# LEDs.net
KiCad netlist of a schematic drawn in Altium Designer
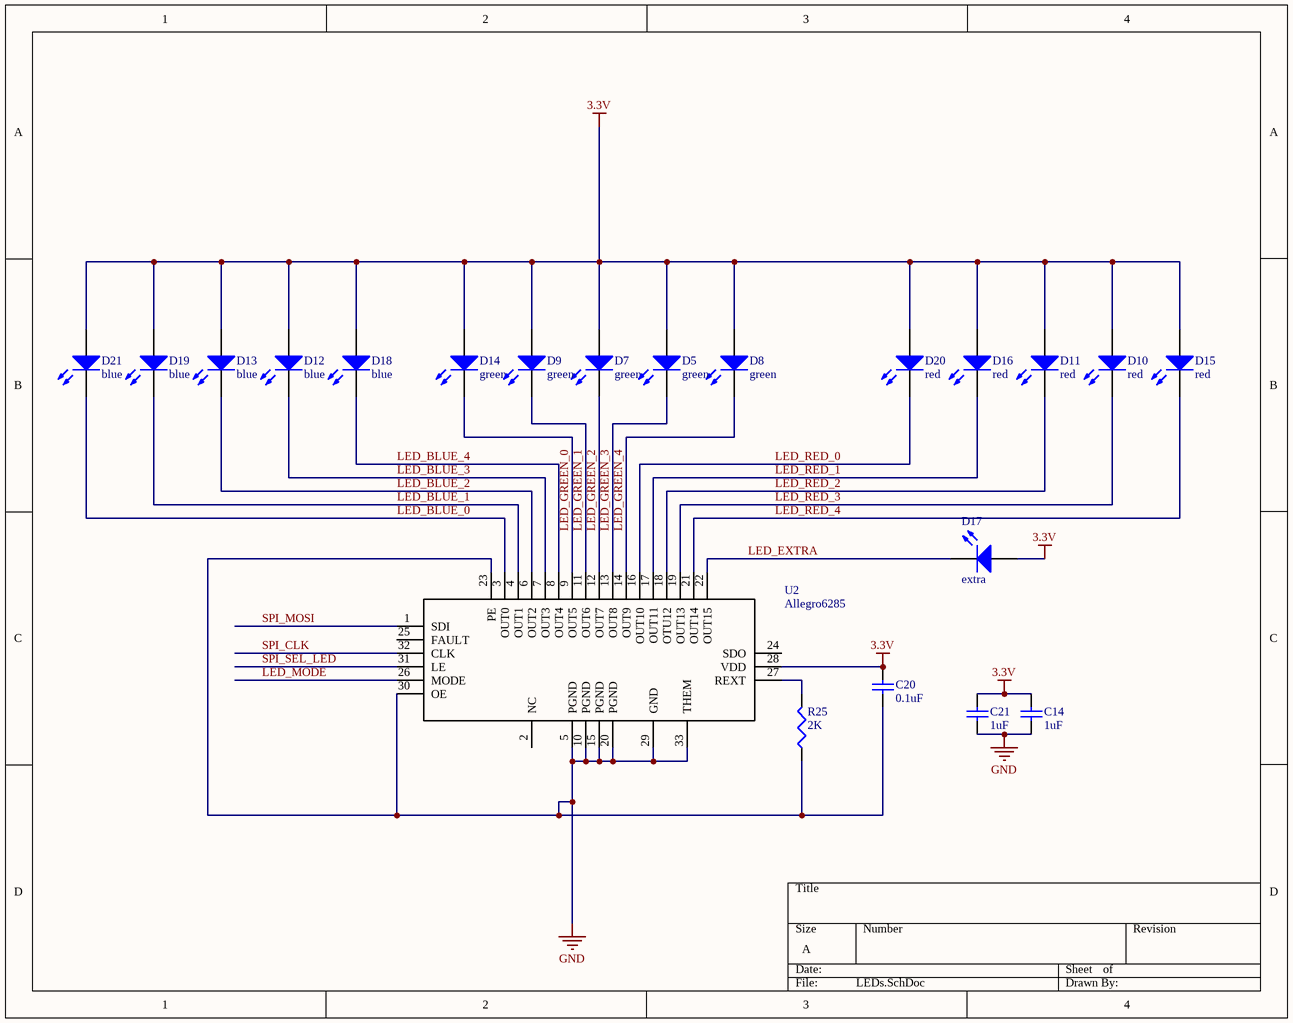
[diagram p0: LEDs.SchDoc]

(export (version "E")
  (design (tool "Eeschema 10.0.6"))
  (components
    (comp (ref "C14")
      (value "1uF")
      (footprint "CAPC1608L")
      (description "Capacitor (Semiconductor SIM Model)")
      (fields (field (name "Comment") "Cap Semi") (field (name "PUBLISHER") "Altium Limited"))
      (libsource (lib "Miscellaneous Devices") (part "Cap Semi"))
    )
    (comp (ref "C20")
      (value "0.1uF")
      (footprint "CAPC1005L")
      (description "Capacitor (Semiconductor SIM Model)")
      (fields (field (name "Comment") "Cap Semi") (field (name "PUBLISHER") "Altium Limited"))
      (libsource (lib "Miscellaneous Devices") (part "Cap Semi"))
    )
    (comp (ref "C21")
      (value "1uF")
      (footprint "CAPC1608L")
      (description "Capacitor (Semiconductor SIM Model)")
      (fields (field (name "Comment") "Cap Semi") (field (name "PUBLISHER") "Altium Limited"))
      (libsource (lib "Miscellaneous Devices") (part "Cap Semi"))
    )
    (comp (ref "D5") (value "green") (footprint "SurfaceMount(603)") (libsource (lib "mrone") (part "LED")))
    (comp (ref "D7") (value "green") (footprint "SurfaceMount(603)") (libsource (lib "mrone") (part "LED")))
    (comp (ref "D8") (value "green") (footprint "SurfaceMount(603)") (libsource (lib "mrone") (part "LED")))
    (comp (ref "D9") (value "green") (footprint "SurfaceMount(603)") (libsource (lib "mrone") (part "LED")))
    (comp (ref "D10") (value "red") (footprint "SurfaceMount(603)") (libsource (lib "mrone") (part "LED")))
    (comp (ref "D11") (value "red") (footprint "SurfaceMount(603)") (libsource (lib "mrone") (part "LED")))
    (comp (ref "D12") (value "blue") (footprint "SurfaceMount(603)") (libsource (lib "mrone") (part "LED")))
    (comp (ref "D13") (value "blue") (footprint "SurfaceMount(603)") (libsource (lib "mrone") (part "LED")))
    (comp (ref "D14") (value "green") (footprint "SurfaceMount(603)") (libsource (lib "mrone") (part "LED")))
    (comp (ref "D15") (value "red") (footprint "SurfaceMount(603)") (libsource (lib "mrone") (part "LED")))
    (comp (ref "D16") (value "red") (footprint "SurfaceMount(603)") (libsource (lib "mrone") (part "LED")))
    (comp (ref "D17") (value "extra") (footprint "SurfaceMount(603)") (libsource (lib "") (part "LED_1")))
    (comp (ref "D18") (value "blue") (footprint "SurfaceMount(603)") (libsource (lib "mrone") (part "LED")))
    (comp (ref "D19") (value "blue") (footprint "SurfaceMount(603)") (libsource (lib "mrone") (part "LED")))
    (comp (ref "D20") (value "red") (footprint "SurfaceMount(603)") (libsource (lib "mrone") (part "LED")))
    (comp (ref "D21") (value "blue") (footprint "SurfaceMount(603)") (libsource (lib "mrone") (part "LED")))
    (comp (ref "R25")
      (value "2K")
      (footprint "RESC1608L")
      (description "Resistor")
      (fields (field (name "Comment") "Res3") (field (name "PUBLISHER") "Altium Limited"))
      (libsource (lib "Miscellaneous Devices") (part "Res3"))
    )
    (comp (ref "U2")
      (value "Allegro6285")
      (footprint "QFN-32")
      (libsource (lib "mrone") (part "Allegro6285"))
    )
  )
  (nets
    (net (code "1") (name "/LED_BLUE_0") (class "Default")
      (node (ref "D21") (pin "2") (pinfunction "K_2") (pintype "passive"))
      (node (ref "U2") (pin "3") (pinfunction "OUT0_3") (pintype "passive"))
    )
    (net (code "2") (name "/LED_BLUE_1") (class "Default")
      (node (ref "D19") (pin "2") (pinfunction "K_2") (pintype "passive"))
      (node (ref "U2") (pin "4") (pinfunction "OUT1_4") (pintype "passive"))
    )
    (net (code "3") (name "/LED_BLUE_2") (class "Default")
      (node (ref "D13") (pin "2") (pinfunction "K_2") (pintype "passive"))
      (node (ref "U2") (pin "6") (pinfunction "OUT2_6") (pintype "passive"))
    )
    (net (code "4") (name "/LED_BLUE_3") (class "Default")
      (node (ref "D12") (pin "2") (pinfunction "K_2") (pintype "passive"))
      (node (ref "U2") (pin "7") (pinfunction "OUT3_7") (pintype "passive"))
    )
    (net (code "5") (name "/LED_BLUE_4") (class "Default")
      (node (ref "D18") (pin "2") (pinfunction "K_2") (pintype "passive"))
      (node (ref "U2") (pin "8") (pinfunction "OUT4_8") (pintype "passive"))
    )
    (net (code "6") (name "/LED_EXTRA") (class "Default")
      (node (ref "D17") (pin "2") (pinfunction "K_2") (pintype "passive"))
      (node (ref "U2") (pin "22") (pinfunction "OUT15_22") (pintype "passive"))
    )
    (net (code "7") (name "/LED_GREEN_0") (class "Default")
      (node (ref "D14") (pin "2") (pinfunction "K_2") (pintype "passive"))
      (node (ref "U2") (pin "9") (pinfunction "OUT5_9") (pintype "passive"))
    )
    (net (code "8") (name "/LED_GREEN_1") (class "Default")
      (node (ref "D9") (pin "2") (pinfunction "K_2") (pintype "passive"))
      (node (ref "U2") (pin "11") (pinfunction "OUT6_11") (pintype "passive"))
    )
    (net (code "9") (name "/LED_GREEN_2") (class "Default")
      (node (ref "D7") (pin "2") (pinfunction "K_2") (pintype "passive"))
      (node (ref "U2") (pin "12") (pinfunction "OUT7_12") (pintype "passive"))
    )
    (net (code "10") (name "/LED_GREEN_3") (class "Default")
      (node (ref "D5") (pin "2") (pinfunction "K_2") (pintype "passive"))
      (node (ref "U2") (pin "13") (pinfunction "OUT8_13") (pintype "passive"))
    )
    (net (code "11") (name "/LED_GREEN_4") (class "Default")
      (node (ref "D8") (pin "2") (pinfunction "K_2") (pintype "passive"))
      (node (ref "U2") (pin "14") (pinfunction "OUT9_14") (pintype "passive"))
    )
    (net (code "12") (name "/LED_MODE") (class "Default")
      (node (ref "U2") (pin "26") (pinfunction "MODE_26") (pintype "passive"))
    )
    (net (code "13") (name "/LED_RED_0") (class "Default")
      (node (ref "D20") (pin "2") (pinfunction "K_2") (pintype "passive"))
      (node (ref "U2") (pin "16") (pinfunction "OUT10_16") (pintype "passive"))
    )
    (net (code "14") (name "/LED_RED_1") (class "Default")
      (node (ref "D16") (pin "2") (pinfunction "K_2") (pintype "passive"))
      (node (ref "U2") (pin "17") (pinfunction "OUT11_17") (pintype "passive"))
    )
    (net (code "15") (name "/LED_RED_2") (class "Default")
      (node (ref "D11") (pin "2") (pinfunction "K_2") (pintype "passive"))
      (node (ref "U2") (pin "18") (pinfunction "OTU12_18") (pintype "passive"))
    )
    (net (code "16") (name "/LED_RED_3") (class "Default")
      (node (ref "D10") (pin "2") (pinfunction "K_2") (pintype "passive"))
      (node (ref "U2") (pin "19") (pinfunction "OUT13_19") (pintype "passive"))
    )
    (net (code "17") (name "/LED_RED_4") (class "Default")
      (node (ref "D15") (pin "2") (pinfunction "K_2") (pintype "passive"))
      (node (ref "U2") (pin "21") (pinfunction "OUT14_21") (pintype "passive"))
    )
    (net (code "18") (name "/SPI_CLK") (class "Default")
      (node (ref "U2") (pin "32") (pinfunction "CLK_32") (pintype "passive"))
    )
    (net (code "19") (name "/SPI_MOSI") (class "Default")
      (node (ref "U2") (pin "1") (pinfunction "SDI_1") (pintype "passive"))
    )
    (net (code "20") (name "/SPI_SEL_LED") (class "Default")
      (node (ref "U2") (pin "31") (pinfunction "LE_31") (pintype "passive"))
    )
    (net (code "21") (name "3.3V") (class "Default")
      (node (ref "C14") (pin "2") (pinfunction "2_2") (pintype "passive"))
      (node (ref "C20") (pin "2") (pinfunction "2_2") (pintype "passive"))
      (node (ref "C21") (pin "2") (pinfunction "2_2") (pintype "passive"))
      (node (ref "D10") (pin "1") (pinfunction "A_1") (pintype "passive"))
      (node (ref "D11") (pin "1") (pinfunction "A_1") (pintype "passive"))
      (node (ref "D12") (pin "1") (pinfunction "A_1") (pintype "passive"))
      (node (ref "D13") (pin "1") (pinfunction "A_1") (pintype "passive"))
      (node (ref "D14") (pin "1") (pinfunction "A_1") (pintype "passive"))
      (node (ref "D15") (pin "1") (pinfunction "A_1") (pintype "passive"))
      (node (ref "D16") (pin "1") (pinfunction "A_1") (pintype "passive"))
      (node (ref "D17") (pin "1") (pinfunction "A_1") (pintype "passive"))
      (node (ref "D18") (pin "1") (pinfunction "A_1") (pintype "passive"))
      (node (ref "D19") (pin "1") (pinfunction "A_1") (pintype "passive"))
      (node (ref "D20") (pin "1") (pinfunction "A_1") (pintype "passive"))
      (node (ref "D21") (pin "1") (pinfunction "A_1") (pintype "passive"))
      (node (ref "D5") (pin "1") (pinfunction "A_1") (pintype "passive"))
      (node (ref "D7") (pin "1") (pinfunction "A_1") (pintype "passive"))
      (node (ref "D8") (pin "1") (pinfunction "A_1") (pintype "passive"))
      (node (ref "D9") (pin "1") (pinfunction "A_1") (pintype "passive"))
      (node (ref "U2") (pin "28") (pinfunction "VDD_28") (pintype "passive"))
    )
    (net (code "22") (name "GND") (class "Default")
      (node (ref "C14") (pin "1") (pinfunction "1_1") (pintype "passive"))
      (node (ref "C20") (pin "1") (pinfunction "1_1") (pintype "passive"))
      (node (ref "C21") (pin "1") (pinfunction "1_1") (pintype "passive"))
      (node (ref "R25") (pin "1") (pinfunction "1_1") (pintype "passive"))
      (node (ref "U2") (pin "10") (pinfunction "PGND_10") (pintype "passive"))
      (node (ref "U2") (pin "15") (pinfunction "PGND_15") (pintype "passive"))
      (node (ref "U2") (pin "20") (pinfunction "PGND_20") (pintype "passive"))
      (node (ref "U2") (pin "23") (pinfunction "PE_23") (pintype "passive"))
      (node (ref "U2") (pin "29") (pinfunction "GND_29") (pintype "passive"))
      (node (ref "U2") (pin "30") (pinfunction "OE_30") (pintype "passive"))
      (node (ref "U2") (pin "33") (pinfunction "THEM_33") (pintype "passive"))
      (node (ref "U2") (pin "5") (pinfunction "PGND_5") (pintype "passive"))
    )
    (net (code "23") (name "Net-(U2-REXT)") (class "Default")
      (node (ref "R25") (pin "2") (pinfunction "2_2") (pintype "passive"))
      (node (ref "U2") (pin "27") (pinfunction "REXT_27") (pintype "passive"))
    )
    (net (code "24") (name "unconnected-(U2-FAULT-Pad25)") (class "Default")
      (node (ref "U2") (pin "25") (pinfunction "FAULT_25") (pintype "passive"))
    )
    (net (code "25") (name "unconnected-(U2-NC-Pad2)") (class "Default")
      (node (ref "U2") (pin "2") (pinfunction "NC_2") (pintype "passive"))
    )
    (net (code "26") (name "unconnected-(U2-SDO-Pad24)") (class "Default")
      (node (ref "U2") (pin "24") (pinfunction "SDO_24") (pintype "passive"))
    )
  )
)
